# tombol.net
KiCad netlist of a schematic drawn in EAGLE
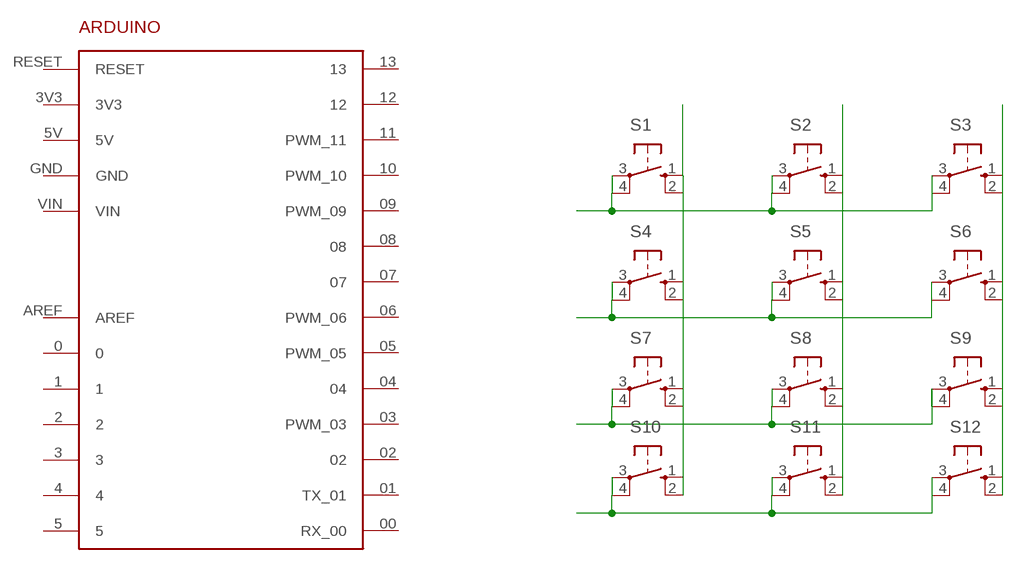
[diagram p0: schematic, sheet 1]

(export (version "E")
  (design (tool "Eeschema 10.0.6"))
  (components
    (comp (ref "ARDUINO1")
      (value "ARDUINO")
      (footprint "eagle-import:ARDUINO")
      (libsource (lib "eagle-import") (part "ARDUINO"))
    )
    (comp (ref "S1")
      (value "10-XX")
      (footprint "eagle-import:B3F-10XX")
      (fields (field (name "MPN") "B3F-1000"))
      (libsource (lib "eagle-import") (part "10-XX"))
    )
    (comp (ref "S2")
      (value "10-XX")
      (footprint "eagle-import:B3F-10XX")
      (fields (field (name "MPN") "B3F-1000"))
      (libsource (lib "eagle-import") (part "10-XX"))
    )
    (comp (ref "S3")
      (value "10-XX")
      (footprint "eagle-import:B3F-10XX")
      (fields (field (name "MPN") "B3F-1000"))
      (libsource (lib "eagle-import") (part "10-XX"))
    )
    (comp (ref "S4")
      (value "10-XX")
      (footprint "eagle-import:B3F-10XX")
      (fields (field (name "MPN") "B3F-1000"))
      (libsource (lib "eagle-import") (part "10-XX"))
    )
    (comp (ref "S5")
      (value "10-XX")
      (footprint "eagle-import:B3F-10XX")
      (fields (field (name "MPN") "B3F-1000"))
      (libsource (lib "eagle-import") (part "10-XX"))
    )
    (comp (ref "S6")
      (value "10-XX")
      (footprint "eagle-import:B3F-10XX")
      (fields (field (name "MPN") "B3F-1000"))
      (libsource (lib "eagle-import") (part "10-XX"))
    )
    (comp (ref "S7")
      (value "10-XX")
      (footprint "eagle-import:B3F-10XX")
      (fields (field (name "MPN") "B3F-1000"))
      (libsource (lib "eagle-import") (part "10-XX"))
    )
    (comp (ref "S8")
      (value "10-XX")
      (footprint "eagle-import:B3F-10XX")
      (fields (field (name "MPN") "B3F-1000"))
      (libsource (lib "eagle-import") (part "10-XX"))
    )
    (comp (ref "S9")
      (value "10-XX")
      (footprint "eagle-import:B3F-10XX")
      (fields (field (name "MPN") "B3F-1000"))
      (libsource (lib "eagle-import") (part "10-XX"))
    )
    (comp (ref "S10")
      (value "10-XX")
      (footprint "eagle-import:B3F-10XX")
      (fields (field (name "MPN") "B3F-1000"))
      (libsource (lib "eagle-import") (part "10-XX"))
    )
    (comp (ref "S11")
      (value "10-XX")
      (footprint "eagle-import:B3F-10XX")
      (fields (field (name "MPN") "B3F-1000"))
      (libsource (lib "eagle-import") (part "10-XX"))
    )
    (comp (ref "S12")
      (value "10-XX")
      (footprint "eagle-import:B3F-10XX")
      (fields (field (name "MPN") "B3F-1000"))
      (libsource (lib "eagle-import") (part "10-XX"))
    )
  )
  (nets
    (net (code "1") (name "Net-(S1-P)") (class "Default")
      (node (ref "S1") (pin "3") (pinfunction "P_3") (pintype "passive"))
      (node (ref "S1") (pin "4") (pinfunction "P1_4") (pintype "passive"))
      (node (ref "S2") (pin "3") (pinfunction "P_3") (pintype "passive"))
      (node (ref "S2") (pin "4") (pinfunction "P1_4") (pintype "passive"))
      (node (ref "S3") (pin "3") (pinfunction "P_3") (pintype "passive"))
      (node (ref "S3") (pin "4") (pinfunction "P1_4") (pintype "passive"))
    )
    (net (code "2") (name "Net-(S1-S)") (class "Default")
      (node (ref "S1") (pin "1") (pinfunction "S_1") (pintype "passive"))
      (node (ref "S1") (pin "2") (pinfunction "S1_2") (pintype "passive"))
      (node (ref "S10") (pin "1") (pinfunction "S_1") (pintype "passive"))
      (node (ref "S10") (pin "2") (pinfunction "S1_2") (pintype "passive"))
      (node (ref "S4") (pin "1") (pinfunction "S_1") (pintype "passive"))
      (node (ref "S4") (pin "2") (pinfunction "S1_2") (pintype "passive"))
      (node (ref "S7") (pin "1") (pinfunction "S_1") (pintype "passive"))
      (node (ref "S7") (pin "2") (pinfunction "S1_2") (pintype "passive"))
    )
    (net (code "3") (name "Net-(S4-P)") (class "Default")
      (node (ref "S4") (pin "3") (pinfunction "P_3") (pintype "passive"))
      (node (ref "S4") (pin "4") (pinfunction "P1_4") (pintype "passive"))
      (node (ref "S5") (pin "3") (pinfunction "P_3") (pintype "passive"))
      (node (ref "S5") (pin "4") (pinfunction "P1_4") (pintype "passive"))
      (node (ref "S6") (pin "3") (pinfunction "P_3") (pintype "passive"))
      (node (ref "S6") (pin "4") (pinfunction "P1_4") (pintype "passive"))
    )
    (net (code "4") (name "Net-(S7-P)") (class "Default")
      (node (ref "S7") (pin "3") (pinfunction "P_3") (pintype "passive"))
      (node (ref "S7") (pin "4") (pinfunction "P1_4") (pintype "passive"))
      (node (ref "S8") (pin "3") (pinfunction "P_3") (pintype "passive"))
      (node (ref "S8") (pin "4") (pinfunction "P1_4") (pintype "passive"))
      (node (ref "S9") (pin "3") (pinfunction "P_3") (pintype "passive"))
      (node (ref "S9") (pin "4") (pinfunction "P1_4") (pintype "passive"))
    )
    (net (code "5") (name "Net-(S10-P)") (class "Default")
      (node (ref "S10") (pin "3") (pinfunction "P_3") (pintype "passive"))
      (node (ref "S10") (pin "4") (pinfunction "P1_4") (pintype "passive"))
      (node (ref "S11") (pin "3") (pinfunction "P_3") (pintype "passive"))
      (node (ref "S11") (pin "4") (pinfunction "P1_4") (pintype "passive"))
      (node (ref "S12") (pin "3") (pinfunction "P_3") (pintype "passive"))
      (node (ref "S12") (pin "4") (pinfunction "P1_4") (pintype "passive"))
    )
    (net (code "6") (name "Net-(S11-S)") (class "Default")
      (node (ref "S11") (pin "1") (pinfunction "S_1") (pintype "passive"))
      (node (ref "S11") (pin "2") (pinfunction "S1_2") (pintype "passive"))
      (node (ref "S2") (pin "1") (pinfunction "S_1") (pintype "passive"))
      (node (ref "S2") (pin "2") (pinfunction "S1_2") (pintype "passive"))
      (node (ref "S5") (pin "1") (pinfunction "S_1") (pintype "passive"))
      (node (ref "S5") (pin "2") (pinfunction "S1_2") (pintype "passive"))
      (node (ref "S8") (pin "1") (pinfunction "S_1") (pintype "passive"))
      (node (ref "S8") (pin "2") (pinfunction "S1_2") (pintype "passive"))
    )
    (net (code "7") (name "Net-(S12-S)") (class "Default")
      (node (ref "S12") (pin "1") (pinfunction "S_1") (pintype "passive"))
      (node (ref "S12") (pin "2") (pinfunction "S1_2") (pintype "passive"))
      (node (ref "S3") (pin "1") (pinfunction "S_1") (pintype "passive"))
      (node (ref "S3") (pin "2") (pinfunction "S1_2") (pintype "passive"))
      (node (ref "S6") (pin "1") (pinfunction "S_1") (pintype "passive"))
      (node (ref "S6") (pin "2") (pinfunction "S1_2") (pintype "passive"))
      (node (ref "S9") (pin "1") (pinfunction "S_1") (pintype "passive"))
      (node (ref "S9") (pin "2") (pinfunction "S1_2") (pintype "passive"))
    )
    (net (code "8") (name "unconnected-(ARDUINO1-PWM_03-Pad03)") (class "Default")
      (node (ref "ARDUINO1") (pin "03") (pinfunction "PWM_03_03") (pintype "bidirectional"))
    )
    (net (code "9") (name "unconnected-(ARDUINO1-PWM_05-Pad05)") (class "Default")
      (node (ref "ARDUINO1") (pin "05") (pinfunction "PWM_05_05") (pintype "bidirectional"))
    )
    (net (code "10") (name "unconnected-(ARDUINO1-PWM_06-Pad06)") (class "Default")
      (node (ref "ARDUINO1") (pin "06") (pinfunction "PWM_06_06") (pintype "bidirectional"))
    )
    (net (code "11") (name "unconnected-(ARDUINO1-PWM_09-Pad09)") (class "Default")
      (node (ref "ARDUINO1") (pin "09") (pinfunction "PWM_09_09") (pintype "bidirectional"))
    )
    (net (code "12") (name "unconnected-(ARDUINO1-PWM_10-Pad10)") (class "Default")
      (node (ref "ARDUINO1") (pin "10") (pinfunction "PWM_10_10") (pintype "bidirectional"))
    )
    (net (code "13") (name "unconnected-(ARDUINO1-PWM_11-Pad11)") (class "Default")
      (node (ref "ARDUINO1") (pin "11") (pinfunction "PWM_11_11") (pintype "bidirectional"))
    )
    (net (code "14") (name "unconnected-(ARDUINO1-Pad0)") (class "Default")
      (node (ref "ARDUINO1") (pin "0") (pinfunction "0_0") (pintype "bidirectional"))
    )
    (net (code "15") (name "unconnected-(ARDUINO1-Pad1)") (class "Default")
      (node (ref "ARDUINO1") (pin "1") (pinfunction "1_1") (pintype "bidirectional"))
    )
    (net (code "16") (name "unconnected-(ARDUINO1-Pad2)") (class "Default")
      (node (ref "ARDUINO1") (pin "2") (pinfunction "2_2") (pintype "bidirectional"))
    )
    (net (code "17") (name "unconnected-(ARDUINO1-Pad02)") (class "Default")
      (node (ref "ARDUINO1") (pin "02") (pinfunction "02_02") (pintype "bidirectional"))
    )
    (net (code "18") (name "unconnected-(ARDUINO1-Pad3)") (class "Default")
      (node (ref "ARDUINO1") (pin "3") (pinfunction "3_3") (pintype "bidirectional"))
    )
    (net (code "19") (name "unconnected-(ARDUINO1-Pad3V3)") (class "Default")
      (node (ref "ARDUINO1") (pin "3V3") (pinfunction "3V3_3V3") (pintype "bidirectional"))
    )
    (net (code "20") (name "unconnected-(ARDUINO1-Pad4)") (class "Default")
      (node (ref "ARDUINO1") (pin "4") (pinfunction "4_4") (pintype "bidirectional"))
    )
    (net (code "21") (name "unconnected-(ARDUINO1-Pad04)") (class "Default")
      (node (ref "ARDUINO1") (pin "04") (pinfunction "04_04") (pintype "bidirectional"))
    )
    (net (code "22") (name "unconnected-(ARDUINO1-Pad5)") (class "Default")
      (node (ref "ARDUINO1") (pin "5") (pinfunction "5_5") (pintype "bidirectional"))
    )
    (net (code "23") (name "unconnected-(ARDUINO1-Pad5V)") (class "Default")
      (node (ref "ARDUINO1") (pin "5V") (pinfunction "5V_5V") (pintype "bidirectional"))
    )
    (net (code "24") (name "unconnected-(ARDUINO1-Pad07)") (class "Default")
      (node (ref "ARDUINO1") (pin "07") (pinfunction "07_07") (pintype "bidirectional"))
    )
    (net (code "25") (name "unconnected-(ARDUINO1-Pad08)") (class "Default")
      (node (ref "ARDUINO1") (pin "08") (pinfunction "08_08") (pintype "bidirectional"))
    )
    (net (code "26") (name "unconnected-(ARDUINO1-Pad12)") (class "Default")
      (node (ref "ARDUINO1") (pin "12") (pinfunction "12_12") (pintype "bidirectional"))
    )
    (net (code "27") (name "unconnected-(ARDUINO1-Pad13)") (class "Default")
      (node (ref "ARDUINO1") (pin "13") (pinfunction "13_13") (pintype "bidirectional"))
    )
    (net (code "28") (name "unconnected-(ARDUINO1-PadAREF)") (class "Default")
      (node (ref "ARDUINO1") (pin "AREF") (pinfunction "AREF_AREF") (pintype "bidirectional"))
    )
    (net (code "29") (name "unconnected-(ARDUINO1-PadGND)") (class "Default")
      (node (ref "ARDUINO1") (pin "GND") (pinfunction "GND_GND") (pintype "bidirectional"))
    )
    (net (code "30") (name "unconnected-(ARDUINO1-PadRESET)") (class "Default")
      (node (ref "ARDUINO1") (pin "RESET") (pinfunction "RESET_RESET") (pintype "bidirectional"))
    )
    (net (code "31") (name "unconnected-(ARDUINO1-PadVIN)") (class "Default")
      (node (ref "ARDUINO1") (pin "VIN") (pinfunction "VIN_VIN") (pintype "bidirectional"))
    )
    (net (code "32") (name "unconnected-(ARDUINO1-RX_00-Pad00)") (class "Default")
      (node (ref "ARDUINO1") (pin "00") (pinfunction "RX_00_00") (pintype "bidirectional"))
    )
    (net (code "33") (name "unconnected-(ARDUINO1-TX_01-Pad01)") (class "Default")
      (node (ref "ARDUINO1") (pin "01") (pinfunction "TX_01_01") (pintype "bidirectional"))
    )
  )
)
